# 7I92FPGA.net
KiCad netlist of a schematic drawn in Altium Designer
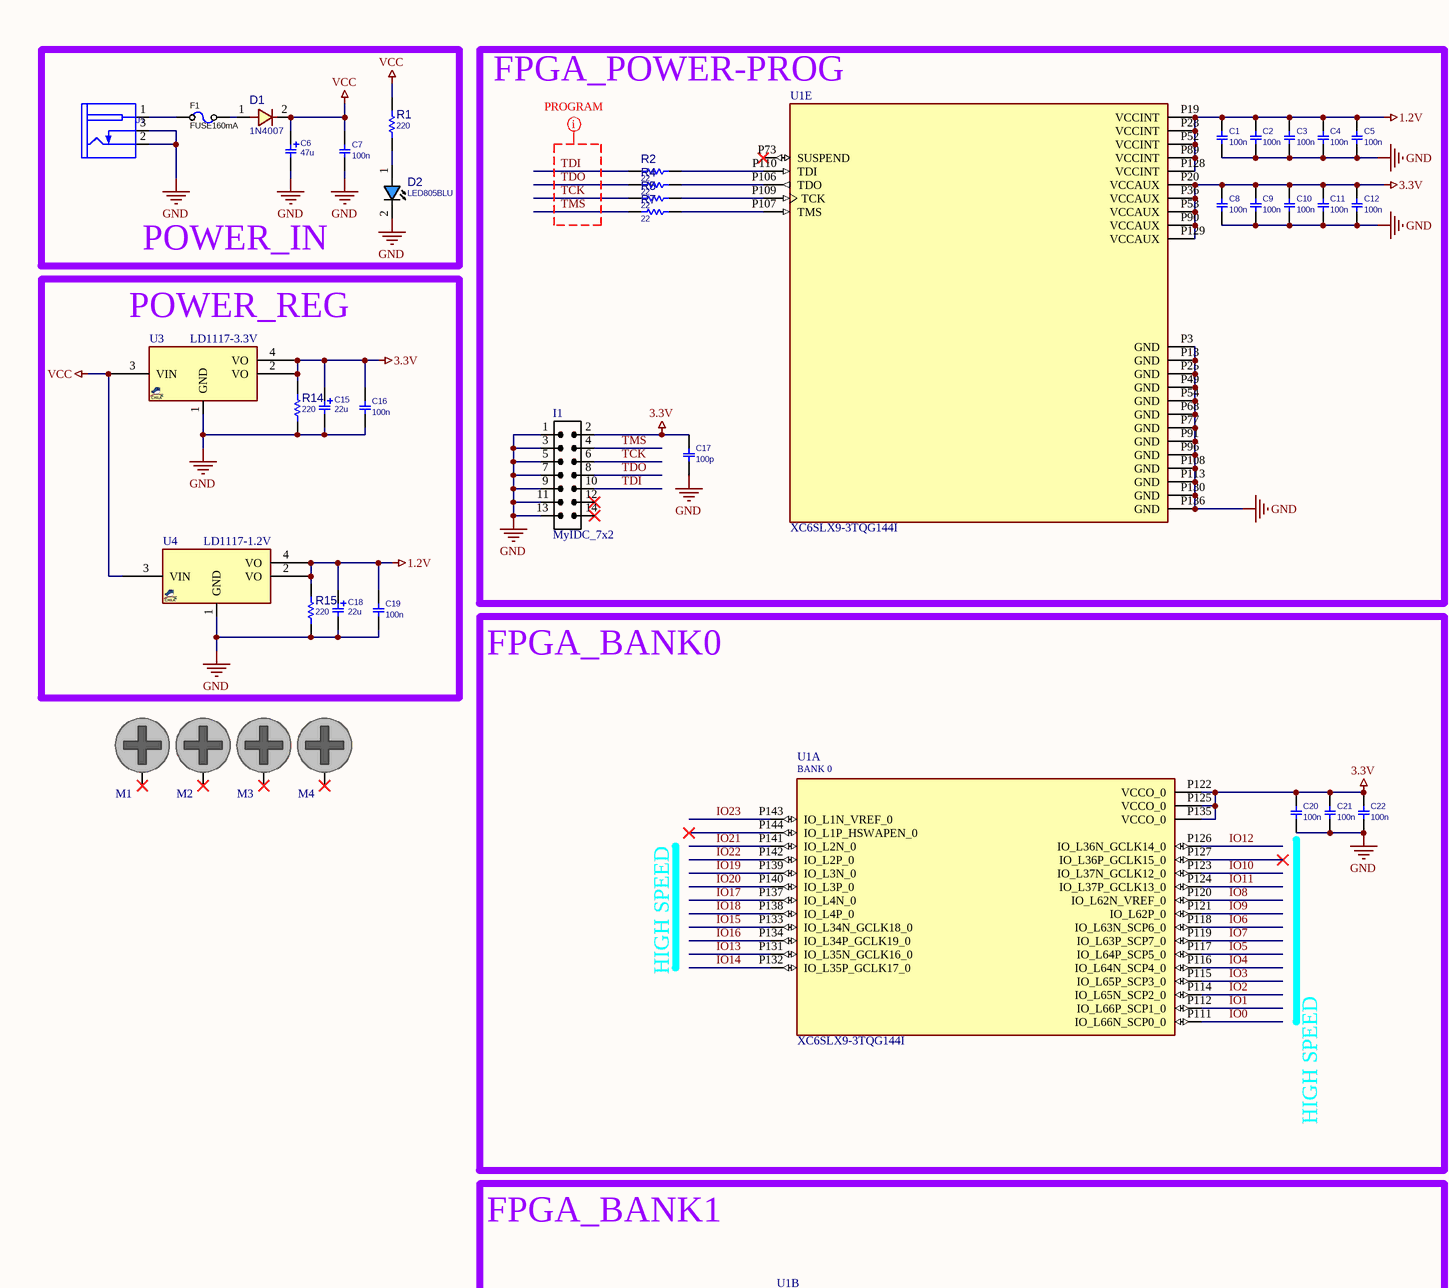
[diagram p0: 7I92FPGA.SchDoc, top left]
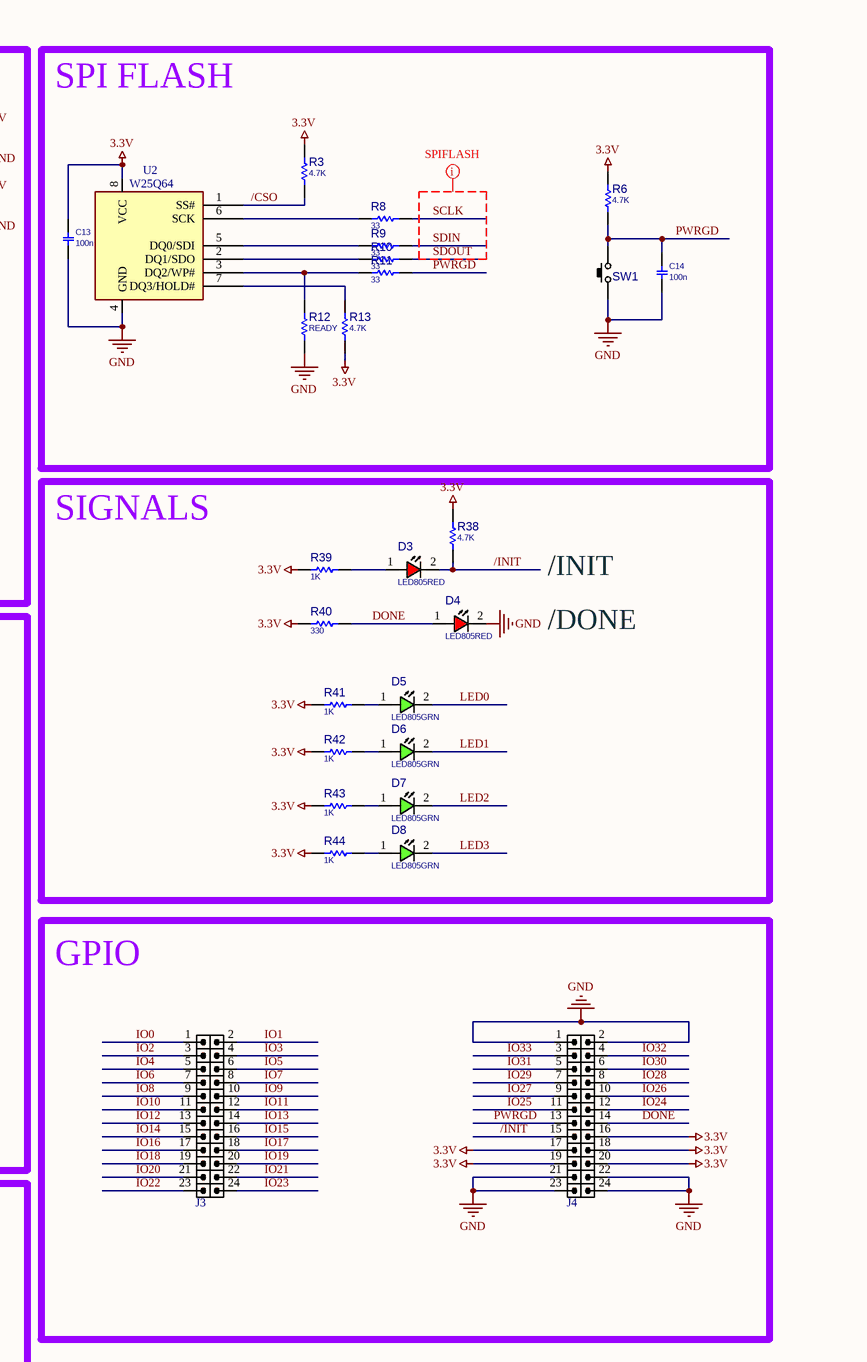
[diagram p1: 7I92FPGA.SchDoc, top middle]
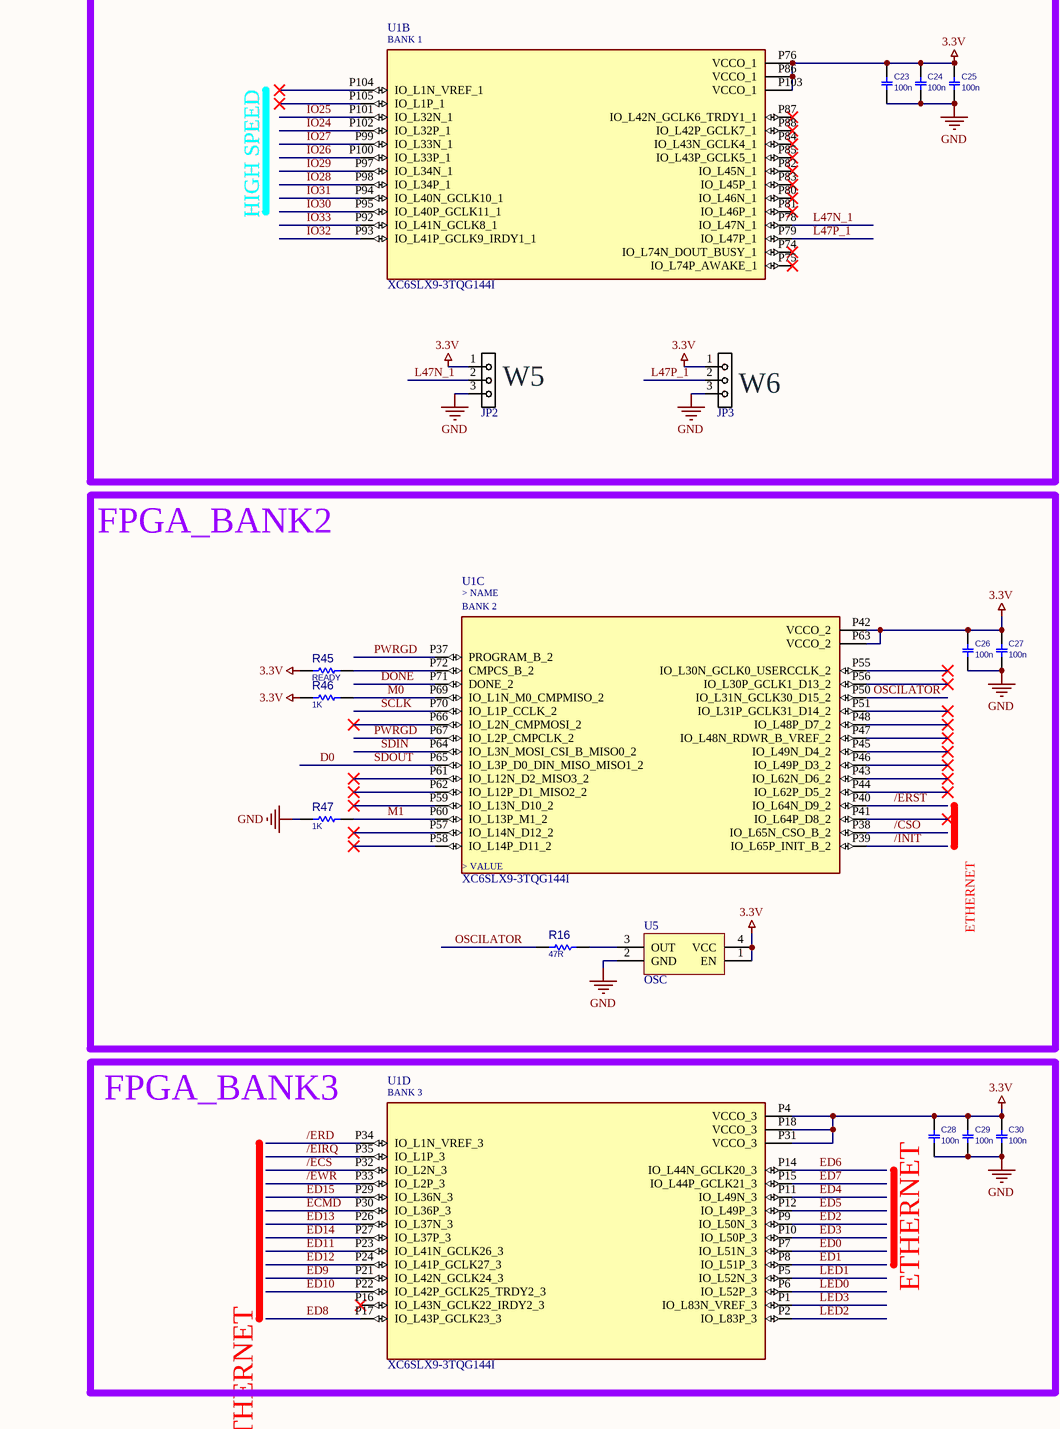
[diagram p2: 7I92FPGA.SchDoc, bottom left]
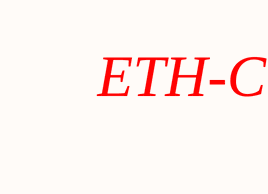
[diagram p3: 7I92FPGA.SchDoc, bottom right]

(export (version "E")
  (design (tool "Eeschema 10.0.6"))
  (components
    (comp (ref "C1")
      (value "100n")
      (footprint "C0603")
      (description "CAP, MLCC, 1nF, 50V, C0G, 10%, 0402")
      (fields (field (name "MANF") "Murata"))
      (libsource (lib "Full_libraries") (part "CAP_SMD_MLCC"))
    )
    (comp (ref "C2")
      (value "100n")
      (footprint "C0603")
      (description "CAP, MLCC, 1nF, 50V, C0G, 10%, 0402")
      (fields (field (name "MANF") "Murata"))
      (libsource (lib "Full_libraries") (part "CAP_SMD_MLCC"))
    )
    (comp (ref "C3")
      (value "100n")
      (footprint "C0603")
      (description "CAP, MLCC, 1nF, 50V, C0G, 10%, 0402")
      (fields (field (name "MANF") "Murata"))
      (libsource (lib "Full_libraries") (part "CAP_SMD_MLCC"))
    )
    (comp (ref "C4")
      (value "100n")
      (footprint "C0603")
      (description "CAP, MLCC, 1nF, 50V, C0G, 10%, 0402")
      (fields (field (name "MANF") "Murata"))
      (libsource (lib "Full_libraries") (part "CAP_SMD_MLCC"))
    )
    (comp (ref "C5")
      (value "100n")
      (footprint "C0603")
      (description "CAP, MLCC, 1nF, 50V, C0G, 10%, 0402")
      (fields (field (name "MANF") "Murata"))
      (libsource (lib "Full_libraries") (part "CAP_SMD_MLCC"))
    )
    (comp (ref "C6")
      (value "47u")
      (footprint "C_TN_3216")
      (description "CAP, SMD, TAN,")
      (libsource (lib "Full_libraries") (part "CAP_SMD_TAN"))
    )
    (comp (ref "C7")
      (value "100n")
      (footprint "C0805")
      (description "CAP, MLCC, 1nF, 50V, C0G, 10%, 0402")
      (fields (field (name "MANF") "Murata"))
      (libsource (lib "Full_libraries") (part "CAP_SMD_MLCC"))
    )
    (comp (ref "C8")
      (value "100n")
      (footprint "C0603")
      (description "CAP, MLCC, 1nF, 50V, C0G, 10%, 0402")
      (fields (field (name "MANF") "Murata"))
      (libsource (lib "Full_libraries") (part "CAP_SMD_MLCC"))
    )
    (comp (ref "C9")
      (value "100n")
      (footprint "C0603")
      (description "CAP, MLCC, 1nF, 50V, C0G, 10%, 0402")
      (fields (field (name "MANF") "Murata"))
      (libsource (lib "Full_libraries") (part "CAP_SMD_MLCC"))
    )
    (comp (ref "C10")
      (value "100n")
      (footprint "C0603")
      (description "CAP, MLCC, 1nF, 50V, C0G, 10%, 0402")
      (fields (field (name "MANF") "Murata"))
      (libsource (lib "Full_libraries") (part "CAP_SMD_MLCC"))
    )
    (comp (ref "C11")
      (value "100n")
      (footprint "C0603")
      (description "CAP, MLCC, 1nF, 50V, C0G, 10%, 0402")
      (fields (field (name "MANF") "Murata"))
      (libsource (lib "Full_libraries") (part "CAP_SMD_MLCC"))
    )
    (comp (ref "C12")
      (value "100n")
      (footprint "C0603")
      (description "CAP, MLCC, 1nF, 50V, C0G, 10%, 0402")
      (fields (field (name "MANF") "Murata"))
      (libsource (lib "Full_libraries") (part "CAP_SMD_MLCC"))
    )
    (comp (ref "C13")
      (value "100n")
      (footprint "C0603")
      (description "CAP, MLCC, 1nF, 50V, C0G, 10%, 0402")
      (fields (field (name "MANF") "Murata"))
      (libsource (lib "Full_libraries") (part "CAP_SMD_MLCC"))
    )
    (comp (ref "C14")
      (value "100n")
      (footprint "C0603")
      (description "CAP, MLCC, 1nF, 50V, C0G, 10%, 0402")
      (fields (field (name "MANF") "Murata"))
      (libsource (lib "Full_libraries") (part "CAP_SMD_MLCC"))
    )
    (comp (ref "C15")
      (value "22u")
      (footprint "C_TN_3216")
      (description "CAP, SMD, TAN,")
      (libsource (lib "Full_libraries") (part "CAP_SMD_TAN"))
    )
    (comp (ref "C16")
      (value "100n")
      (footprint "C0805")
      (description "CAP, MLCC, 1nF, 50V, C0G, 10%, 0402")
      (fields (field (name "MANF") "Murata"))
      (libsource (lib "Full_libraries") (part "CAP_SMD_MLCC"))
    )
    (comp (ref "C17")
      (value "100p")
      (footprint "C0603")
      (description "CAP, MLCC, 1nF, 50V, C0G, 10%, 0402")
      (fields (field (name "MANF") "Murata"))
      (libsource (lib "Full_libraries") (part "CAP_SMD_MLCC"))
    )
    (comp (ref "C18")
      (value "22u")
      (footprint "C_TN_3216")
      (description "CAP, SMD, TAN,")
      (libsource (lib "Full_libraries") (part "CAP_SMD_TAN"))
    )
    (comp (ref "C19")
      (value "100n")
      (footprint "C0805")
      (description "CAP, MLCC, 1nF, 50V, C0G, 10%, 0402")
      (fields (field (name "MANF") "Murata"))
      (libsource (lib "Full_libraries") (part "CAP_SMD_MLCC"))
    )
    (comp (ref "C20")
      (value "100n")
      (footprint "C0603")
      (description "CAP, MLCC, 1nF, 50V, C0G, 10%, 0402")
      (fields (field (name "MANF") "Murata"))
      (libsource (lib "Full_libraries") (part "CAP_SMD_MLCC"))
    )
    (comp (ref "C21")
      (value "100n")
      (footprint "C0603")
      (description "CAP, MLCC, 1nF, 50V, C0G, 10%, 0402")
      (fields (field (name "MANF") "Murata"))
      (libsource (lib "Full_libraries") (part "CAP_SMD_MLCC"))
    )
    (comp (ref "C22")
      (value "100n")
      (footprint "C0603")
      (description "CAP, MLCC, 1nF, 50V, C0G, 10%, 0402")
      (fields (field (name "MANF") "Murata"))
      (libsource (lib "Full_libraries") (part "CAP_SMD_MLCC"))
    )
    (comp (ref "C23")
      (value "100n")
      (footprint "C0603")
      (description "CAP, MLCC, 1nF, 50V, C0G, 10%, 0402")
      (fields (field (name "MANF") "Murata"))
      (libsource (lib "Full_libraries") (part "CAP_SMD_MLCC"))
    )
    (comp (ref "C24")
      (value "100n")
      (footprint "C0603")
      (description "CAP, MLCC, 1nF, 50V, C0G, 10%, 0402")
      (fields (field (name "MANF") "Murata"))
      (libsource (lib "Full_libraries") (part "CAP_SMD_MLCC"))
    )
    (comp (ref "C25")
      (value "100n")
      (footprint "C0603")
      (description "CAP, MLCC, 1nF, 50V, C0G, 10%, 0402")
      (fields (field (name "MANF") "Murata"))
      (libsource (lib "Full_libraries") (part "CAP_SMD_MLCC"))
    )
    (comp (ref "C26")
      (value "100n")
      (footprint "C0603")
      (description "CAP, MLCC, 1nF, 50V, C0G, 10%, 0402")
      (fields (field (name "MANF") "Murata"))
      (libsource (lib "Full_libraries") (part "CAP_SMD_MLCC"))
    )
    (comp (ref "C27")
      (value "100n")
      (footprint "C0603")
      (description "CAP, MLCC, 1nF, 50V, C0G, 10%, 0402")
      (fields (field (name "MANF") "Murata"))
      (libsource (lib "Full_libraries") (part "CAP_SMD_MLCC"))
    )
    (comp (ref "C28")
      (value "100n")
      (footprint "C0603")
      (description "CAP, MLCC, 1nF, 50V, C0G, 10%, 0402")
      (fields (field (name "MANF") "Murata"))
      (libsource (lib "Full_libraries") (part "CAP_SMD_MLCC"))
    )
    (comp (ref "C29")
      (value "100n")
      (footprint "C0603")
      (description "CAP, MLCC, 1nF, 50V, C0G, 10%, 0402")
      (fields (field (name "MANF") "Murata"))
      (libsource (lib "Full_libraries") (part "CAP_SMD_MLCC"))
    )
    (comp (ref "C30")
      (value "100n")
      (footprint "C0603")
      (description "CAP, MLCC, 1nF, 50V, C0G, 10%, 0402")
      (fields (field (name "MANF") "Murata"))
      (libsource (lib "Full_libraries") (part "CAP_SMD_MLCC"))
    )
    (comp (ref "D1")
      (value "1N4007")
      (footprint "D_SMA")
      (description "DIODE, GENERAL PURPOSE, 1000V/1A")
      (fields (field (name "MANF") "Kingtronics") (field (name "MANF_P#") "M7"))
      (libsource (lib "Full_libraries") (part "DIODE_SMD_1N4007"))
    )
    (comp (ref "D2")
      (value "LED805BLU")
      (footprint "LED0805BLU")
      (description "LED, SMD, 0805, BLUE")
      (fields (field (name "MANF") "MANF") (field (name "MANF_P#") "MANF_PART#"))
      (libsource (lib "Full_libraries") (part "LED_SMD_0805_BLU"))
    )
    (comp (ref "D3")
      (value "LED805RED")
      (footprint "LED0805RED")
      (description "LED, SMD, 0805, RED")
      (fields (field (name "MANF") "MANF") (field (name "MANF_P#") "MANF_PART#"))
      (libsource (lib "Full_libraries") (part "LED_SMD_0805_RED"))
    )
    (comp (ref "D4")
      (value "LED805RED")
      (footprint "LED0805RED")
      (description "LED, SMD, 0805, RED")
      (fields (field (name "MANF") "MANF") (field (name "MANF_P#") "MANF_PART#"))
      (libsource (lib "Full_libraries") (part "LED_SMD_0805_RED"))
    )
    (comp (ref "D5")
      (value "LED805GRN")
      (footprint "LED0805GRN")
      (description "LED, SMD, 0805, GREEN")
      (libsource (lib "Full_libraries") (part "LED_SMD_0805_GRN"))
    )
    (comp (ref "D6")
      (value "LED805GRN")
      (footprint "LED0805GRN")
      (description "LED, SMD, 0805, GREEN")
      (libsource (lib "Full_libraries") (part "LED_SMD_0805_GRN"))
    )
    (comp (ref "D7")
      (value "LED805GRN")
      (footprint "LED0805GRN")
      (description "LED, SMD, 0805, GREEN")
      (libsource (lib "Full_libraries") (part "LED_SMD_0805_GRN"))
    )
    (comp (ref "D8")
      (value "LED805GRN")
      (footprint "LED0805GRN")
      (description "LED, SMD, 0805, GREEN")
      (libsource (lib "Full_libraries") (part "LED_SMD_0805_GRN"))
    )
    (comp (ref "F1")
      (value "FUSE160mA")
      (footprint "F1206")
      (description "Fuse, 160mA, 63VDC, 1206, SMD, Fast Acting")
      (fields (field (name "MANF") "Holly Fuse") (field (name "MANF_P#") "12T-0160L"))
      (libsource (lib "Full_libraries") (part "FUSE_160mA_1206"))
    )
    (comp (ref "I1")
      (value "MyIDC_7x2")
      (footprint "myIDC_7x2")
      (libsource (lib "Full_libraries") (part "MyIDC_7x2"))
    )
    (comp (ref "J1")
      (value "DC_POWER_JACK")
      (footprint "JAC_PWR2")
      (description "CONN, PWR JACK DC, PLUG DIAM 2.0MM RA THD")
      (fields
        (field (name "MANF") "CUI STACK")
        (field (name "MANF_P#") "PJ-202A, PJ-002AH, PJ-102AH, KLDX-0202")
      )
      (libsource (lib "Full_libraries") (part "CONN_PWR_JACKR2"))
    )
    (comp (ref "J3")
      (value "HDRM_2X12")
      (footprint "HDR_M_2X12")
      (description "CONN, HEADER, Male, pitch: 2.54mm, 24POS")
      (libsource (lib "Full_libraries") (part "HDR_M_2X12"))
    )
    (comp (ref "J4")
      (value "HDRM_2X12")
      (footprint "HDR_M_2X12")
      (description "CONN, HEADER, Male, pitch: 2.54mm, 24POS")
      (libsource (lib "Full_libraries") (part "HDR_M_2X12"))
    )
    (comp (ref "JP2")
      (value "JMPHDR3PIN")
      (footprint "JP_3")
      (description "JUMPER, HEADER 3PIN")
      (fields (field (name "MANF") "MANF") (field (name "MANF_P#") "MANF_P#"))
      (libsource (lib "Full_libraries (1)") (part "JUMPER_HDR_3P"))
    )
    (comp (ref "JP3")
      (value "JMPHDR3PIN")
      (footprint "JP_3")
      (description "JUMPER, HEADER 3PIN")
      (fields (field (name "MANF") "MANF") (field (name "MANF_P#") "MANF_P#"))
      (libsource (lib "Full_libraries (1)") (part "JUMPER_HDR_3P"))
    )
    (comp (ref "M1")
      (value "DNP/MH")
      (footprint "SCMH_M4C")
      (description "SCREW mouting, M4, 4mm diameter and 8.0mm CheeseHead")
      (libsource (lib "Full_libraries") (part "SCMH_M4C"))
    )
    (comp (ref "M2")
      (value "DNP/MH")
      (footprint "SCMH_M4C")
      (description "SCREW mouting, M4, 4mm diameter and 8.0mm CheeseHead")
      (libsource (lib "Full_libraries") (part "SCMH_M4C"))
    )
    (comp (ref "M3")
      (value "DNP/MH")
      (footprint "SCMH_M4C")
      (description "SCREW mouting, M4, 4mm diameter and 8.0mm CheeseHead")
      (libsource (lib "Full_libraries") (part "SCMH_M4C"))
    )
    (comp (ref "M4")
      (value "DNP/MH")
      (footprint "SCMH_M4C")
      (description "SCREW mouting, M4, 4mm diameter and 8.0mm CheeseHead")
      (libsource (lib "Full_libraries") (part "SCMH_M4C"))
    )
    (comp (ref "R1")
      (value "220")
      (footprint "R0805")
      (description "RESISTOR, SMD")
      (fields (field (name "MANF_P#") "RK73H1ETTP4701F") (field (name "MANF") "KOA SPEER"))
      (libsource (lib "Full_libraries") (part "RES_SMD"))
    )
    (comp (ref "R2")
      (value "22")
      (footprint "R0603")
      (description "RESISTOR, SMD")
      (fields (field (name "MANF_P#") "RK73H1ETTP4701F") (field (name "MANF") "KOA SPEER"))
      (libsource (lib "Full_libraries") (part "RES_SMD"))
    )
    (comp (ref "R3")
      (value "4.7K")
      (footprint "R0603")
      (description "RESISTOR, SMD")
      (fields (field (name "MANF_P#") "RK73H1ETTP4701F") (field (name "MANF") "KOA SPEER"))
      (libsource (lib "Full_libraries") (part "RES_SMD"))
    )
    (comp (ref "R4")
      (value "22")
      (footprint "R0603")
      (description "RESISTOR, SMD")
      (fields (field (name "MANF_P#") "RK73H1ETTP4701F") (field (name "MANF") "KOA SPEER"))
      (libsource (lib "Full_libraries") (part "RES_SMD"))
    )
    (comp (ref "R5")
      (value "22")
      (footprint "R0603")
      (description "RESISTOR, SMD")
      (fields (field (name "MANF_P#") "RK73H1ETTP4701F") (field (name "MANF") "KOA SPEER"))
      (libsource (lib "Full_libraries") (part "RES_SMD"))
    )
    (comp (ref "R6")
      (value "4.7K")
      (footprint "R0603")
      (description "RESISTOR, SMD")
      (fields (field (name "MANF_P#") "RK73H1ETTP4701F") (field (name "MANF") "KOA SPEER"))
      (libsource (lib "Full_libraries") (part "RES_SMD"))
    )
    (comp (ref "R7")
      (value "22")
      (footprint "R0603")
      (description "RESISTOR, SMD")
      (fields (field (name "MANF_P#") "RK73H1ETTP4701F") (field (name "MANF") "KOA SPEER"))
      (libsource (lib "Full_libraries") (part "RES_SMD"))
    )
    (comp (ref "R8")
      (value "33")
      (footprint "R0603")
      (description "RESISTOR, SMD")
      (fields (field (name "MANF_P#") "RK73H1ETTP4701F") (field (name "MANF") "KOA SPEER"))
      (libsource (lib "Full_libraries") (part "RES_SMD"))
    )
    (comp (ref "R9")
      (value "33")
      (footprint "R0603")
      (description "RESISTOR, SMD")
      (fields (field (name "MANF_P#") "RK73H1ETTP4701F") (field (name "MANF") "KOA SPEER"))
      (libsource (lib "Full_libraries") (part "RES_SMD"))
    )
    (comp (ref "R10")
      (value "33")
      (footprint "R0603")
      (description "RESISTOR, SMD")
      (fields (field (name "MANF_P#") "RK73H1ETTP4701F") (field (name "MANF") "KOA SPEER"))
      (libsource (lib "Full_libraries") (part "RES_SMD"))
    )
    (comp (ref "R11")
      (value "33")
      (footprint "R0603")
      (description "RESISTOR, SMD")
      (fields (field (name "MANF_P#") "RK73H1ETTP4701F") (field (name "MANF") "KOA SPEER"))
      (libsource (lib "Full_libraries") (part "RES_SMD"))
    )
    (comp (ref "R12")
      (value "READY")
      (footprint "R0603")
      (description "RESISTOR, SMD")
      (fields (field (name "MANF_P#") "RK73H1ETTP4701F") (field (name "MANF") "KOA SPEER"))
      (libsource (lib "Full_libraries") (part "RES_SMD"))
    )
    (comp (ref "R13")
      (value "4.7K")
      (footprint "R0603")
      (description "RESISTOR, SMD")
      (fields (field (name "MANF_P#") "RK73H1ETTP4701F") (field (name "MANF") "KOA SPEER"))
      (libsource (lib "Full_libraries") (part "RES_SMD"))
    )
    (comp (ref "R14")
      (value "220")
      (footprint "R0805")
      (description "RESISTOR, SMD")
      (fields (field (name "MANF_P#") "RK73H1ETTP4701F") (field (name "MANF") "KOA SPEER"))
      (libsource (lib "Full_libraries") (part "RES_SMD"))
    )
    (comp (ref "R15")
      (value "220")
      (footprint "R0805")
      (description "RESISTOR, SMD")
      (fields (field (name "MANF_P#") "RK73H1ETTP4701F") (field (name "MANF") "KOA SPEER"))
      (libsource (lib "Full_libraries") (part "RES_SMD"))
    )
    (comp (ref "R16")
      (value "47R")
      (footprint "R0603")
      (description "RESISTOR, SMD")
      (fields (field (name "MANF_P#") "RK73H1ETTP4701F") (field (name "MANF") "KOA SPEER"))
      (libsource (lib "Full_libraries") (part "RES_SMD"))
    )
    (comp (ref "R38")
      (value "4.7K")
      (footprint "R0603")
      (description "RESISTOR, SMD")
      (fields (field (name "MANF_P#") "RK73H1ETTP4701F") (field (name "MANF") "KOA SPEER"))
      (libsource (lib "Full_libraries") (part "RES_SMD"))
    )
    (comp (ref "R39")
      (value "1K")
      (footprint "R0603")
      (description "RESISTOR, SMD")
      (fields (field (name "MANF_P#") "RK73H1ETTP4701F") (field (name "MANF") "KOA SPEER"))
      (libsource (lib "Full_libraries") (part "RES_SMD"))
    )
    (comp (ref "R40")
      (value "330")
      (footprint "R0603")
      (description "RESISTOR, SMD")
      (fields (field (name "MANF_P#") "RK73H1ETTP4701F") (field (name "MANF") "KOA SPEER"))
      (libsource (lib "Full_libraries") (part "RES_SMD"))
    )
    (comp (ref "R41")
      (value "1K")
      (footprint "R0603")
      (description "RESISTOR, SMD")
      (fields (field (name "MANF_P#") "RK73H1ETTP4701F") (field (name "MANF") "KOA SPEER"))
      (libsource (lib "Full_libraries") (part "RES_SMD"))
    )
    (comp (ref "R42")
      (value "1K")
      (footprint "R0603")
      (description "RESISTOR, SMD")
      (fields (field (name "MANF_P#") "RK73H1ETTP4701F") (field (name "MANF") "KOA SPEER"))
      (libsource (lib "Full_libraries") (part "RES_SMD"))
    )
    (comp (ref "R43")
      (value "1K")
      (footprint "R0603")
      (description "RESISTOR, SMD")
      (fields (field (name "MANF_P#") "RK73H1ETTP4701F") (field (name "MANF") "KOA SPEER"))
      (libsource (lib "Full_libraries") (part "RES_SMD"))
    )
    (comp (ref "R44")
      (value "1K")
      (footprint "R0603")
      (description "RESISTOR, SMD")
      (fields (field (name "MANF_P#") "RK73H1ETTP4701F") (field (name "MANF") "KOA SPEER"))
      (libsource (lib "Full_libraries") (part "RES_SMD"))
    )
    (comp (ref "R45")
      (value "READY")
      (footprint "R0603")
      (description "RESISTOR, SMD")
      (fields (field (name "MANF_P#") "RK73H1ETTP4701F") (field (name "MANF") "KOA SPEER"))
      (libsource (lib "Full_libraries") (part "RES_SMD"))
    )
    (comp (ref "R46")
      (value "1K")
      (footprint "R0603")
      (description "RESISTOR, SMD")
      (fields (field (name "MANF_P#") "RK73H1ETTP4701F") (field (name "MANF") "KOA SPEER"))
      (libsource (lib "Full_libraries") (part "RES_SMD"))
    )
    (comp (ref "R47")
      (value "1K")
      (footprint "R0603")
      (description "RESISTOR, SMD")
      (fields (field (name "MANF_P#") "RK73H1ETTP4701F") (field (name "MANF") "KOA SPEER"))
      (libsource (lib "Full_libraries") (part "RES_SMD"))
    )
    (comp (ref "SW1")
      (value "PUSHBUTTON")
      (footprint "SWPBS_SPST_6X3X5")
      (description "SWITCH, PUSH BUTTON, TACTILE, SMD, SPST, 6X3.5X4.3mm")
      (fields (field (name "MANF") "Panasonic") (field (name "MANF_P#") "EVQ-PNF04M"))
      (libsource (lib "Full_libraries") (part "SWPBS_SPST_6X3X4"))
    )
    (comp (ref "U1")
      (value "XC6SLX9-3TQG144I")
      (footprint "QFP50P2200X2200X160-144N")
      (description "FPGA Spartan-6 LX Family 9152 Cells 45nm (CMOS) Technology 1.2V 144-Pin TQFP")
      (fields (field (name "MF") "{'manufacturer': u'Xilinx Inc.'}"))
      (libsource (lib "SnapEDA_Library") (part "XC6SLX9-3TQG144I"))
    )
    (comp (ref "U2")
      (value "W25Q64")
      (footprint "SO_8_W")
      (description "SPI FLASH Memory, 64Mb (8M x8), 104MHz")
      (fields (field (name "MANF") "WINBOND") (field (name "MANF_P#") "W25Q64FVSSIG"))
      (libsource (lib "Full_libraries") (part "W25Q64FV_SO8W"))
    )
    (comp (ref "U3")
      (value "LD1117-3.3V")
      (footprint "SOT223_4")
      (description "REG, Linear, LDO1V, 0.8A, SOT-223")
      (fields
        (field (name "MANF_P#") "LD1117, LM1117, AMS1117, TLV1117, REG1117, NCP1117, LT1117, SPX1117")
        (field (name "MANF") "TI, ON, ST")
      )
      (libsource (lib "Full_libraries") (part "VREG_1117_SOT223"))
    )
    (comp (ref "U4")
      (value "LD1117-1.2V")
      (footprint "SOT223_4")
      (description "REG, Linear, LDO1V, 0.8A, SOT-223")
      (fields
        (field (name "MANF_P#") "LD1117, LM1117, AMS1117, TLV1117, REG1117, NCP1117, LT1117, SPX1117")
        (field (name "MANF") "TI, ON, ST")
      )
      (libsource (lib "Full_libraries") (part "VREG_1117_SOT223"))
    )
    (comp (ref "U5")
      (value "OSC")
      (footprint "XTL_4_7050GEN")
      (libsource (lib "Behyaar_RLCD_v1") (part "OSC (SMD)"))
    )
  )
  (nets
    (net (code "1") (name "/D0") (class "Default")
      (node (ref "R10") (pin "1") (pinfunction "1_1") (pintype "passive"))
      (node (ref "U1") (pin "P65") (pinfunction "IO_L3P_D0_DIN_MISO_MISO1_2_P65") (pintype "bidirectional"))
    )
    (net (code "2") (name "/DONE") (class "Default")
      (node (ref "D4") (pin "1") (pinfunction "ANODE_1") (pintype "passive"))
      (node (ref "J4") (pin "14") (pinfunction "14_14") (pintype "passive"))
      (node (ref "R40") (pin "1") (pinfunction "1_1") (pintype "passive"))
      (node (ref "U1") (pin "P71") (pinfunction "DONE_2_P71") (pintype "bidirectional"))
    )
    (net (code "3") (name "/ECMD") (class "Default")
      (node (ref "U1") (pin "P30") (pinfunction "IO_L36P_3_P30") (pintype "bidirectional"))
    )
    (net (code "4") (name "/ED0") (class "Default")
      (node (ref "U1") (pin "P7") (pinfunction "IO_L51N_3_P7") (pintype "bidirectional"))
    )
    (net (code "5") (name "/ED1") (class "Default")
      (node (ref "U1") (pin "P8") (pinfunction "IO_L51P_3_P8") (pintype "bidirectional"))
    )
    (net (code "6") (name "/ED2") (class "Default")
      (node (ref "U1") (pin "P9") (pinfunction "IO_L50N_3_P9") (pintype "bidirectional"))
    )
    (net (code "7") (name "/ED3") (class "Default")
      (node (ref "U1") (pin "P10") (pinfunction "IO_L50P_3_P10") (pintype "bidirectional"))
    )
    (net (code "8") (name "/ED4") (class "Default")
      (node (ref "U1") (pin "P11") (pinfunction "IO_L49N_3_P11") (pintype "bidirectional"))
    )
    (net (code "9") (name "/ED5") (class "Default")
      (node (ref "U1") (pin "P12") (pinfunction "IO_L49P_3_P12") (pintype "bidirectional"))
    )
    (net (code "10") (name "/ED6") (class "Default")
      (node (ref "U1") (pin "P14") (pinfunction "IO_L44N_GCLK20_3_P14") (pintype "bidirectional"))
    )
    (net (code "11") (name "/ED7") (class "Default")
      (node (ref "U1") (pin "P15") (pinfunction "IO_L44P_GCLK21_3_P15") (pintype "bidirectional"))
    )
    (net (code "12") (name "/ED8") (class "Default")
      (node (ref "U1") (pin "P17") (pinfunction "IO_L43P_GCLK23_3_P17") (pintype "bidirectional"))
    )
    (net (code "13") (name "/ED9") (class "Default")
      (node (ref "U1") (pin "P21") (pinfunction "IO_L42N_GCLK24_3_P21") (pintype "bidirectional"))
    )
    (net (code "14") (name "/ED10") (class "Default")
      (node (ref "U1") (pin "P22") (pinfunction "IO_L42P_GCLK25_TRDY2_3_P22") (pintype "bidirectional"))
    )
    (net (code "15") (name "/ED11") (class "Default")
      (node (ref "U1") (pin "P23") (pinfunction "IO_L41N_GCLK26_3_P23") (pintype "bidirectional"))
    )
    (net (code "16") (name "/ED12") (class "Default")
      (node (ref "U1") (pin "P24") (pinfunction "IO_L41P_GCLK27_3_P24") (pintype "bidirectional"))
    )
    (net (code "17") (name "/ED13") (class "Default")
      (node (ref "U1") (pin "P26") (pinfunction "IO_L37N_3_P26") (pintype "bidirectional"))
    )
    (net (code "18") (name "/ED14") (class "Default")
      (node (ref "U1") (pin "P27") (pinfunction "IO_L37P_3_P27") (pintype "bidirectional"))
    )
    (net (code "19") (name "/ED15") (class "Default")
      (node (ref "U1") (pin "P29") (pinfunction "IO_L36N_3_P29") (pintype "bidirectional"))
    )
    (net (code "20") (name "/IO0") (class "Default")
      (node (ref "J3") (pin "1") (pinfunction "1_1") (pintype "passive"))
      (node (ref "U1") (pin "P111") (pinfunction "IO_L66N_SCP0_0_P111") (pintype "bidirectional"))
    )
    (net (code "21") (name "/IO1") (class "Default")
      (node (ref "J3") (pin "2") (pinfunction "2_2") (pintype "passive"))
      (node (ref "U1") (pin "P112") (pinfunction "IO_L66P_SCP1_0_P112") (pintype "bidirectional"))
    )
    (net (code "22") (name "/IO2") (class "Default")
      (node (ref "J3") (pin "3") (pinfunction "3_3") (pintype "passive"))
      (node (ref "U1") (pin "P114") (pinfunction "IO_L65N_SCP2_0_P114") (pintype "bidirectional"))
    )
    (net (code "23") (name "/IO3") (class "Default")
      (node (ref "J3") (pin "4") (pinfunction "4_4") (pintype "passive"))
      (node (ref "U1") (pin "P115") (pinfunction "IO_L65P_SCP3_0_P115") (pintype "bidirectional"))
    )
    (net (code "24") (name "/IO4") (class "Default")
      (node (ref "J3") (pin "5") (pinfunction "5_5") (pintype "passive"))
      (node (ref "U1") (pin "P116") (pinfunction "IO_L64N_SCP4_0_P116") (pintype "bidirectional"))
    )
    (net (code "25") (name "/IO5") (class "Default")
      (node (ref "J3") (pin "6") (pinfunction "6_6") (pintype "passive"))
      (node (ref "U1") (pin "P117") (pinfunction "IO_L64P_SCP5_0_P117") (pintype "bidirectional"))
    )
    (net (code "26") (name "/IO6") (class "Default")
      (node (ref "J3") (pin "7") (pinfunction "7_7") (pintype "passive"))
      (node (ref "U1") (pin "P118") (pinfunction "IO_L63N_SCP6_0_P118") (pintype "bidirectional"))
    )
    (net (code "27") (name "/IO7") (class "Default")
      (node (ref "J3") (pin "8") (pinfunction "8_8") (pintype "passive"))
      (node (ref "U1") (pin "P119") (pinfunction "IO_L63P_SCP7_0_P119") (pintype "bidirectional"))
    )
    (net (code "28") (name "/IO8") (class "Default")
      (node (ref "J3") (pin "9") (pinfunction "9_9") (pintype "passive"))
      (node (ref "U1") (pin "P120") (pinfunction "IO_L62N_VREF_0_P120") (pintype "bidirectional"))
    )
    (net (code "29") (name "/IO9") (class "Default")
      (node (ref "J3") (pin "10") (pinfunction "10_10") (pintype "passive"))
      (node (ref "U1") (pin "P121") (pinfunction "IO_L62P_0_P121") (pintype "bidirectional"))
    )
    (net (code "30") (name "/IO10") (class "Default")
      (node (ref "J3") (pin "11") (pinfunction "11_11") (pintype "passive"))
      (node (ref "U1") (pin "P123") (pinfunction "IO_L37N_GCLK12_0_P123") (pintype "bidirectional"))
    )
    (net (code "31") (name "/IO11") (class "Default")
      (node (ref "J3") (pin "12") (pinfunction "12_12") (pintype "passive"))
      (node (ref "U1") (pin "P124") (pinfunction "IO_L37P_GCLK13_0_P124") (pintype "bidirectional"))
    )
    (net (code "32") (name "/IO12") (class "Default")
      (node (ref "J3") (pin "13") (pinfunction "13_13") (pintype "passive"))
      (node (ref "U1") (pin "P126") (pinfunction "IO_L36N_GCLK14_0_P126") (pintype "bidirectional"))
    )
    (net (code "33") (name "/IO13") (class "Default")
      (node (ref "J3") (pin "14") (pinfunction "14_14") (pintype "passive"))
      (node (ref "U1") (pin "P131") (pinfunction "IO_L35N_GCLK16_0_P131") (pintype "bidirectional"))
    )
    (net (code "34") (name "/IO14") (class "Default")
      (node (ref "J3") (pin "15") (pinfunction "15_15") (pintype "passive"))
      (node (ref "U1") (pin "P132") (pinfunction "IO_L35P_GCLK17_0_P132") (pintype "bidirectional"))
    )
    (net (code "35") (name "/IO15") (class "Default")
      (node (ref "J3") (pin "16") (pinfunction "16_16") (pintype "passive"))
      (node (ref "U1") (pin "P133") (pinfunction "IO_L34N_GCLK18_0_P133") (pintype "bidirectional"))
    )
    (net (code "36") (name "/IO16") (class "Default")
      (node (ref "J3") (pin "17") (pinfunction "17_17") (pintype "passive"))
      (node (ref "U1") (pin "P134") (pinfunction "IO_L34P_GCLK19_0_P134") (pintype "bidirectional"))
    )
    (net (code "37") (name "/IO17") (class "Default")
      (node (ref "J3") (pin "18") (pinfunction "18_18") (pintype "passive"))
      (node (ref "U1") (pin "P137") (pinfunction "IO_L4N_0_P137") (pintype "bidirectional"))
    )
    (net (code "38") (name "/IO18") (class "Default")
      (node (ref "J3") (pin "19") (pinfunction "19_19") (pintype "passive"))
      (node (ref "U1") (pin "P138") (pinfunction "IO_L4P_0_P138") (pintype "bidirectional"))
    )
    (net (code "39") (name "/IO19") (class "Default")
      (node (ref "J3") (pin "20") (pinfunction "20_20") (pintype "passive"))
      (node (ref "U1") (pin "P139") (pinfunction "IO_L3N_0_P139") (pintype "bidirectional"))
    )
    (net (code "40") (name "/IO20") (class "Default")
      (node (ref "J3") (pin "21") (pinfunction "21_21") (pintype "passive"))
      (node (ref "U1") (pin "P140") (pinfunction "IO_L3P_0_P140") (pintype "bidirectional"))
    )
    (net (code "41") (name "/IO21") (class "Default")
      (node (ref "J3") (pin "22") (pinfunction "22_22") (pintype "passive"))
      (node (ref "U1") (pin "P141") (pinfunction "IO_L2N_0_P141") (pintype "bidirectional"))
    )
    (net (code "42") (name "/IO22") (class "Default")
      (node (ref "J3") (pin "23") (pinfunction "23_23") (pintype "passive"))
      (node (ref "U1") (pin "P142") (pinfunction "IO_L2P_0_P142") (pintype "bidirectional"))
    )
    (net (code "43") (name "/IO23") (class "Default")
      (node (ref "J3") (pin "24") (pinfunction "24_24") (pintype "passive"))
      (node (ref "U1") (pin "P143") (pinfunction "IO_L1N_VREF_0_P143") (pintype "bidirectional"))
    )
    (net (code "44") (name "/IO24") (class "Default")
      (node (ref "J4") (pin "12") (pinfunction "12_12") (pintype "passive"))
      (node (ref "U1") (pin "P102") (pinfunction "IO_L32P_1_P102") (pintype "bidirectional"))
    )
    (net (code "45") (name "/IO25") (class "Default")
      (node (ref "J4") (pin "11") (pinfunction "11_11") (pintype "passive"))
      (node (ref "U1") (pin "P101") (pinfunction "IO_L32N_1_P101") (pintype "bidirectional"))
    )
    (net (code "46") (name "/IO26") (class "Default")
      (node (ref "J4") (pin "10") (pinfunction "10_10") (pintype "passive"))
      (node (ref "U1") (pin "P100") (pinfunction "IO_L33P_1_P100") (pintype "bidirectional"))
    )
    (net (code "47") (name "/IO27") (class "Default")
      (node (ref "J4") (pin "9") (pinfunction "9_9") (pintype "passive"))
      (node (ref "U1") (pin "P99") (pinfunction "IO_L33N_1_P99") (pintype "bidirectional"))
    )
    (net (code "48") (name "/IO28") (class "Default")
      (node (ref "J4") (pin "8") (pinfunction "8_8") (pintype "passive"))
      (node (ref "U1") (pin "P98") (pinfunction "IO_L34P_1_P98") (pintype "bidirectional"))
    )
    (net (code "49") (name "/IO29") (class "Default")
      (node (ref "J4") (pin "7") (pinfunction "7_7") (pintype "passive"))
      (node (ref "U1") (pin "P97") (pinfunction "IO_L34N_1_P97") (pintype "bidirectional"))
    )
    (net (code "50") (name "/IO30") (class "Default")
      (node (ref "J4") (pin "6") (pinfunction "6_6") (pintype "passive"))
      (node (ref "U1") (pin "P95") (pinfunction "IO_L40P_GCLK11_1_P95") (pintype "bidirectional"))
    )
    (net (code "51") (name "/IO31") (class "Default")
      (node (ref "J4") (pin "5") (pinfunction "5_5") (pintype "passive"))
      (node (ref "U1") (pin "P94") (pinfunction "IO_L40N_GCLK10_1_P94") (pintype "bidirectional"))
    )
    (net (code "52") (name "/IO32") (class "Default")
      (node (ref "J4") (pin "4") (pinfunction "4_4") (pintype "passive"))
      (node (ref "U1") (pin "P93") (pinfunction "IO_L41P_GCLK9_IRDY1_1_P93") (pintype "bidirectional"))
    )
    (net (code "53") (name "/IO33") (class "Default")
      (node (ref "J4") (pin "3") (pinfunction "3_3") (pintype "passive"))
      (node (ref "U1") (pin "P92") (pinfunction "IO_L41N_GCLK8_1_P92") (pintype "bidirectional"))
    )
    (net (code "54") (name "/L47N_1") (class "Default")
      (node (ref "JP2") (pin "2") (pinfunction "2_2") (pintype "passive"))
      (node (ref "U1") (pin "P78") (pinfunction "IO_L47N_1_P78") (pintype "bidirectional"))
    )
    (net (code "55") (name "/L47P_1") (class "Default")
      (node (ref "JP3") (pin "2") (pinfunction "2_2") (pintype "passive"))
      (node (ref "U1") (pin "P79") (pinfunction "IO_L47P_1_P79") (pintype "bidirectional"))
    )
    (net (code "56") (name "/LED0") (class "Default")
      (node (ref "D5") (pin "2") (pinfunction "CATHODE_2") (pintype "passive"))
      (node (ref "U1") (pin "P6") (pinfunction "IO_L52P_3_P6") (pintype "bidirectional"))
    )
    (net (code "57") (name "/LED1") (class "Default")
      (node (ref "D6") (pin "2") (pinfunction "CATHODE_2") (pintype "passive"))
      (node (ref "U1") (pin "P5") (pinfunction "IO_L52N_3_P5") (pintype "bidirectional"))
    )
    (net (code "58") (name "/LED2") (class "Default")
      (node (ref "D7") (pin "2") (pinfunction "CATHODE_2") (pintype "passive"))
      (node (ref "U1") (pin "P2") (pinfunction "IO_L83P_3_P2") (pintype "bidirectional"))
    )
    (net (code "59") (name "/LED3") (class "Default")
      (node (ref "D8") (pin "2") (pinfunction "CATHODE_2") (pintype "passive"))
      (node (ref "U1") (pin "P1") (pinfunction "IO_L83N_VREF_3_P1") (pintype "bidirectional"))
    )
    (net (code "60") (name "/M0") (class "Default")
      (node (ref "R46") (pin "1") (pinfunction "1_1") (pintype "passive"))
      (node (ref "U1") (pin "P69") (pinfunction "IO_L1N_M0_CMPMISO_2_P69") (pintype "bidirectional"))
    )
    (net (code "61") (name "/M1") (class "Default")
      (node (ref "R47") (pin "1") (pinfunction "1_1") (pintype "passive"))
      (node (ref "U1") (pin "P60") (pinfunction "IO_L13P_M1_2_P60") (pintype "bidirectional"))
    )
    (net (code "62") (name "/OSCILATOR") (class "Default")
      (node (ref "R16") (pin "1") (pinfunction "1_1") (pintype "passive"))
      (node (ref "U1") (pin "P50") (pinfunction "IO_L31N_GCLK30_D15_2_P50") (pintype "bidirectional"))
    )
    (net (code "63") (name "/PWRGD") (class "Default")
      (node (ref "C14") (pin "1") (pinfunction "1_1") (pintype "passive"))
      (node (ref "J4") (pin "13") (pinfunction "13_13") (pintype "passive"))
      (node (ref "R11") (pin "1") (pinfunction "1_1") (pintype "passive"))
      (node (ref "R6") (pin "1") (pinfunction "1_1") (pintype "passive"))
      (node (ref "SW1") (pin "2") (pinfunction "P3_2") (pintype "passive"))
      (node (ref "U1") (pin "P37") (pinfunction "PROGRAM_B_2_P37") (pintype "bidirectional"))
      (node (ref "U1") (pin "P67") (pinfunction "IO_L2P_CMPCLK_2_P67") (pintype "bidirectional"))
    )
    (net (code "64") (name "/SCLK") (class "Default")
      (node (ref "R8") (pin "1") (pinfunction "1_1") (pintype "passive"))
      (node (ref "U1") (pin "P70") (pinfunction "IO_L1P_CCLK_2_P70") (pintype "bidirectional"))
    )
    (net (code "65") (name "/SDIN") (class "Default")
      (node (ref "R9") (pin "1") (pinfunction "1_1") (pintype "passive"))
      (node (ref "U1") (pin "P64") (pinfunction "IO_L3N_MOSI_CSI_B_MISO0_2_P64") (pintype "bidirectional"))
    )
    (net (code "66") (name "/TCK") (class "Default")
      (node (ref "I1") (pin "6") (pinfunction "6_6") (pintype "passive"))
      (node (ref "R5") (pin "2") (pinfunction "2_2") (pintype "passive"))
    )
    (net (code "67") (name "/TDI") (class "Default")
      (node (ref "I1") (pin "10") (pinfunction "10_10") (pintype "passive"))
      (node (ref "R2") (pin "2") (pinfunction "2_2") (pintype "passive"))
    )
    (net (code "68") (name "/TDO") (class "Default")
      (node (ref "I1") (pin "8") (pinfunction "8_8") (pintype "passive"))
      (node (ref "R4") (pin "2") (pinfunction "2_2") (pintype "passive"))
    )
    (net (code "69") (name "/TMS") (class "Default")
      (node (ref "I1") (pin "4") (pinfunction "4_4") (pintype "passive"))
      (node (ref "R7") (pin "2") (pinfunction "2_2") (pintype "passive"))
    )
    (net (code "70") (name "/{slash}CSO") (class "Default")
      (node (ref "R3") (pin "1") (pinfunction "1_1") (pintype "passive"))
      (node (ref "U1") (pin "P38") (pinfunction "IO_L65N_CSO_B_2_P38") (pintype "bidirectional"))
      (node (ref "U2") (pin "1") (pinfunction "SS#_1") (pintype "passive"))
    )
    (net (code "71") (name "/{slash}ECS") (class "Default")
      (node (ref "U1") (pin "P32") (pinfunction "IO_L2N_3_P32") (pintype "bidirectional"))
    )
    (net (code "72") (name "/{slash}EIRQ") (class "Default")
      (node (ref "U1") (pin "P35") (pinfunction "IO_L1P_3_P35") (pintype "bidirectional"))
    )
    (net (code "73") (name "/{slash}ERD") (class "Default")
      (node (ref "U1") (pin "P34") (pinfunction "IO_L1N_VREF_3_P34") (pintype "bidirectional"))
    )
    (net (code "74") (name "/{slash}ERST") (class "Default")
      (node (ref "U1") (pin "P40") (pinfunction "IO_L64N_D9_2_P40") (pintype "bidirectional"))
    )
    (net (code "75") (name "/{slash}EWR") (class "Default")
      (node (ref "U1") (pin "P33") (pinfunction "IO_L2P_3_P33") (pintype "bidirectional"))
    )
    (net (code "76") (name "/{slash}INIT") (class "Default")
      (node (ref "D3") (pin "2") (pinfunction "CATHODE_2") (pintype "passive"))
      (node (ref "J4") (pin "15") (pinfunction "15_15") (pintype "passive"))
      (node (ref "R38") (pin "2") (pinfunction "2_2") (pintype "passive"))
      (node (ref "U1") (pin "P39") (pinfunction "IO_L65P_INIT_B_2_P39") (pintype "bidirectional"))
    )
    (net (code "77") (name "1.2V") (class "Default")
      (node (ref "C1") (pin "1") (pinfunction "1_1") (pintype "passive"))
      (node (ref "C18") (pin "1") (pinfunction "1_1") (pintype "passive"))
      (node (ref "C19") (pin "1") (pinfunction "1_1") (pintype "passive"))
      (node (ref "C2") (pin "1") (pinfunction "1_1") (pintype "passive"))
      (node (ref "C3") (pin "1") (pinfunction "1_1") (pintype "passive"))
      (node (ref "C4") (pin "1") (pinfunction "1_1") (pintype "passive"))
      (node (ref "C5") (pin "1") (pinfunction "1_1") (pintype "passive"))
      (node (ref "R15") (pin "1") (pinfunction "1_1") (pintype "passive"))
      (node (ref "U1") (pin "P128") (pinfunction "VCCINT_P128") (pintype "power_in"))
      (node (ref "U1") (pin "P19") (pinfunction "VCCINT_P19") (pintype "power_in"))
      (node (ref "U1") (pin "P28") (pinfunction "VCCINT_P28") (pintype "power_in"))
      (node (ref "U1") (pin "P52") (pinfunction "VCCINT_P52") (pintype "power_in"))
      (node (ref "U1") (pin "P89") (pinfunction "VCCINT_P89") (pintype "power_in"))
      (node (ref "U4") (pin "2") (pinfunction "VO_2") (pintype "passive"))
      (node (ref "U4") (pin "4") (pinfunction "VO_4") (pintype "passive"))
    )
    (net (code "78") (name "3.3V") (class "Default")
      (node (ref "C10") (pin "1") (pinfunction "1_1") (pintype "passive"))
      (node (ref "C11") (pin "1") (pinfunction "1_1") (pintype "passive"))
      (node (ref "C12") (pin "1") (pinfunction "1_1") (pintype "passive"))
      (node (ref "C13") (pin "1") (pinfunction "1_1") (pintype "passive"))
      (node (ref "C15") (pin "1") (pinfunction "1_1") (pintype "passive"))
      (node (ref "C16") (pin "1") (pinfunction "1_1") (pintype "passive"))
      (node (ref "C17") (pin "1") (pinfunction "1_1") (pintype "passive"))
      (node (ref "C20") (pin "1") (pinfunction "1_1") (pintype "passive"))
      (node (ref "C21") (pin "1") (pinfunction "1_1") (pintype "passive"))
      (node (ref "C22") (pin "1") (pinfunction "1_1") (pintype "passive"))
      (node (ref "C23") (pin "1") (pinfunction "1_1") (pintype "passive"))
      (node (ref "C24") (pin "1") (pinfunction "1_1") (pintype "passive"))
      (node (ref "C25") (pin "1") (pinfunction "1_1") (pintype "passive"))
      (node (ref "C26") (pin "1") (pinfunction "1_1") (pintype "passive"))
      (node (ref "C27") (pin "1") (pinfunction "1_1") (pintype "passive"))
      (node (ref "C28") (pin "1") (pinfunction "1_1") (pintype "passive"))
      (node (ref "C29") (pin "1") (pinfunction "1_1") (pintype "passive"))
      (node (ref "C30") (pin "1") (pinfunction "1_1") (pintype "passive"))
      (node (ref "C8") (pin "1") (pinfunction "1_1") (pintype "passive"))
      (node (ref "C9") (pin "1") (pinfunction "1_1") (pintype "passive"))
      (node (ref "I1") (pin "2") (pinfunction "2_2") (pintype "passive"))
      (node (ref "J4") (pin "16") (pinfunction "16_16") (pintype "passive"))
      (node (ref "J4") (pin "17") (pinfunction "17_17") (pintype "passive"))
      (node (ref "J4") (pin "18") (pinfunction "18_18") (pintype "passive"))
      (node (ref "J4") (pin "19") (pinfunction "19_19") (pintype "passive"))
      (node (ref "J4") (pin "20") (pinfunction "20_20") (pintype "passive"))
      (node (ref "JP2") (pin "1") (pinfunction "1_1") (pintype "passive"))
      (node (ref "JP3") (pin "1") (pinfunction "1_1") (pintype "passive"))
      (node (ref "R13") (pin "1") (pinfunction "1_1") (pintype "passive"))
      (node (ref "R14") (pin "1") (pinfunction "1_1") (pintype "passive"))
      (node (ref "R3") (pin "2") (pinfunction "2_2") (pintype "passive"))
      (node (ref "R38") (pin "1") (pinfunction "1_1") (pintype "passive"))
      (node (ref "R39") (pin "2") (pinfunction "2_2") (pintype "passive"))
      (node (ref "R40") (pin "2") (pinfunction "2_2") (pintype "passive"))
      (node (ref "R41") (pin "2") (pinfunction "2_2") (pintype "passive"))
      (node (ref "R42") (pin "2") (pinfunction "2_2") (pintype "passive"))
      (node (ref "R43") (pin "2") (pinfunction "2_2") (pintype "passive"))
      (node (ref "R44") (pin "2") (pinfunction "2_2") (pintype "passive"))
      (node (ref "R45") (pin "2") (pinfunction "2_2") (pintype "passive"))
      (node (ref "R46") (pin "2") (pinfunction "2_2") (pintype "passive"))
      (node (ref "R6") (pin "2") (pinfunction "2_2") (pintype "passive"))
      (node (ref "U1") (pin "P103") (pinfunction "VCCO_1_P103") (pintype "power_in"))
      (node (ref "U1") (pin "P122") (pinfunction "VCCO_0_P122") (pintype "power_in"))
      (node (ref "U1") (pin "P125") (pinfunction "VCCO_0_P125") (pintype "power_in"))
      (node (ref "U1") (pin "P129") (pinfunction "VCCAUX_P129") (pintype "power_in"))
      (node (ref "U1") (pin "P135") (pinfunction "VCCO_0_P135") (pintype "power_in"))
      (node (ref "U1") (pin "P18") (pinfunction "VCCO_3_P18") (pintype "power_in"))
      (node (ref "U1") (pin "P20") (pinfunction "VCCAUX_P20") (pintype "power_in"))
      (node (ref "U1") (pin "P31") (pinfunction "VCCO_3_P31") (pintype "power_in"))
      (node (ref "U1") (pin "P36") (pinfunction "VCCAUX_P36") (pintype "power_in"))
      (node (ref "U1") (pin "P4") (pinfunction "VCCO_3_P4") (pintype "power_in"))
      (node (ref "U1") (pin "P42") (pinfunction "VCCO_2_P42") (pintype "power_in"))
      (node (ref "U1") (pin "P53") (pinfunction "VCCAUX_P53") (pintype "power_in"))
      (node (ref "U1") (pin "P63") (pinfunction "VCCO_2_P63") (pintype "power_in"))
      (node (ref "U1") (pin "P76") (pinfunction "VCCO_1_P76") (pintype "power_in"))
      (node (ref "U1") (pin "P86") (pinfunction "VCCO_1_P86") (pintype "power_in"))
      (node (ref "U1") (pin "P90") (pinfunction "VCCAUX_P90") (pintype "power_in"))
      (node (ref "U2") (pin "8") (pinfunction "VCC_8") (pintype "passive"))
      (node (ref "U3") (pin "2") (pinfunction "VO_2") (pintype "passive"))
      (node (ref "U3") (pin "4") (pinfunction "VO_4") (pintype "passive"))
      (node (ref "U5") (pin "1") (pinfunction "EN_1") (pintype "passive"))
      (node (ref "U5") (pin "4") (pinfunction "VCC_4") (pintype "passive"))
    )
    (net (code "79") (name "GND") (class "Default")
      (node (ref "C1") (pin "2") (pinfunction "2_2") (pintype "passive"))
      (node (ref "C10") (pin "2") (pinfunction "2_2") (pintype "passive"))
      (node (ref "C11") (pin "2") (pinfunction "2_2") (pintype "passive"))
      (node (ref "C12") (pin "2") (pinfunction "2_2") (pintype "passive"))
      (node (ref "C13") (pin "2") (pinfunction "2_2") (pintype "passive"))
      (node (ref "C14") (pin "2") (pinfunction "2_2") (pintype "passive"))
      (node (ref "C15") (pin "2") (pinfunction "2_2") (pintype "passive"))
      (node (ref "C16") (pin "2") (pinfunction "2_2") (pintype "passive"))
      (node (ref "C17") (pin "2") (pinfunction "2_2") (pintype "passive"))
      (node (ref "C18") (pin "2") (pinfunction "2_2") (pintype "passive"))
      (node (ref "C19") (pin "2") (pinfunction "2_2") (pintype "passive"))
      (node (ref "C2") (pin "2") (pinfunction "2_2") (pintype "passive"))
      (node (ref "C20") (pin "2") (pinfunction "2_2") (pintype "passive"))
      (node (ref "C21") (pin "2") (pinfunction "2_2") (pintype "passive"))
      (node (ref "C22") (pin "2") (pinfunction "2_2") (pintype "passive"))
      (node (ref "C23") (pin "2") (pinfunction "2_2") (pintype "passive"))
      (node (ref "C24") (pin "2") (pinfunction "2_2") (pintype "passive"))
      (node (ref "C25") (pin "2") (pinfunction "2_2") (pintype "passive"))
      (node (ref "C26") (pin "2") (pinfunction "2_2") (pintype "passive"))
      (node (ref "C27") (pin "2") (pinfunction "2_2") (pintype "passive"))
      (node (ref "C28") (pin "2") (pinfunction "2_2") (pintype "passive"))
      (node (ref "C29") (pin "2") (pinfunction "2_2") (pintype "passive"))
      (node (ref "C3") (pin "2") (pinfunction "2_2") (pintype "passive"))
      (node (ref "C30") (pin "2") (pinfunction "2_2") (pintype "passive"))
      (node (ref "C4") (pin "2") (pinfunction "2_2") (pintype "passive"))
      (node (ref "C5") (pin "2") (pinfunction "2_2") (pintype "passive"))
      (node (ref "C6") (pin "2") (pinfunction "2_2") (pintype "passive"))
      (node (ref "C7") (pin "2") (pinfunction "2_2") (pintype "passive"))
      (node (ref "C8") (pin "2") (pinfunction "2_2") (pintype "passive"))
      (node (ref "C9") (pin "2") (pinfunction "2_2") (pintype "passive"))
      (node (ref "D2") (pin "2") (pinfunction "CATHODE_2") (pintype "passive"))
      (node (ref "D4") (pin "2") (pinfunction "CATHODE_2") (pintype "passive"))
      (node (ref "I1") (pin "1") (pinfunction "1_1") (pintype "passive"))
      (node (ref "I1") (pin "11") (pinfunction "11_11") (pintype "passive"))
      (node (ref "I1") (pin "13") (pinfunction "13_13") (pintype "passive"))
      (node (ref "I1") (pin "3") (pinfunction "3_3") (pintype "passive"))
      (node (ref "I1") (pin "5") (pinfunction "5_5") (pintype "passive"))
      (node (ref "I1") (pin "7") (pinfunction "7_7") (pintype "passive"))
      (node (ref "I1") (pin "9") (pinfunction "9_9") (pintype "passive"))
      (node (ref "J1") (pin "2") (pinfunction "SLEEVE_2") (pintype "power_in"))
      (node (ref "J1") (pin "3") (pinfunction "INSERTION_DET_3") (pintype "power_in"))
      (node (ref "J4") (pin "1") (pinfunction "1_1") (pintype "passive"))
      (node (ref "J4") (pin "2") (pinfunction "2_2") (pintype "passive"))
      (node (ref "J4") (pin "21") (pinfunction "21_21") (pintype "passive"))
      (node (ref "J4") (pin "22") (pinfunction "22_22") (pintype "passive"))
      (node (ref "J4") (pin "23") (pinfunction "23_23") (pintype "passive"))
      (node (ref "J4") (pin "24") (pinfunction "24_24") (pintype "passive"))
      (node (ref "JP2") (pin "3") (pinfunction "3_3") (pintype "passive"))
      (node (ref "JP3") (pin "3") (pinfunction "3_3") (pintype "passive"))
      (node (ref "R12") (pin "1") (pinfunction "1_1") (pintype "passive"))
      (node (ref "R14") (pin "2") (pinfunction "2_2") (pintype "passive"))
      (node (ref "R15") (pin "2") (pinfunction "2_2") (pintype "passive"))
      (node (ref "R47") (pin "2") (pinfunction "2_2") (pintype "passive"))
      (node (ref "SW1") (pin "1") (pinfunction "P1_1") (pintype "passive"))
      (node (ref "U1") (pin "P108") (pinfunction "GND_P108") (pintype "power_in"))
      (node (ref "U1") (pin "P113") (pinfunction "GND_P113") (pintype "power_in"))
      (node (ref "U1") (pin "P13") (pinfunction "GND_P13") (pintype "power_in"))
      (node (ref "U1") (pin "P130") (pinfunction "GND_P130") (pintype "power_in"))
      (node (ref "U1") (pin "P136") (pinfunction "GND_P136") (pintype "power_in"))
      (node (ref "U1") (pin "P25") (pinfunction "GND_P25") (pintype "power_in"))
      (node (ref "U1") (pin "P3") (pinfunction "GND_P3") (pintype "power_in"))
      (node (ref "U1") (pin "P49") (pinfunction "GND_P49") (pintype "power_in"))
      (node (ref "U1") (pin "P54") (pinfunction "GND_P54") (pintype "power_in"))
      (node (ref "U1") (pin "P68") (pinfunction "GND_P68") (pintype "power_in"))
      (node (ref "U1") (pin "P77") (pinfunction "GND_P77") (pintype "power_in"))
      (node (ref "U1") (pin "P91") (pinfunction "GND_P91") (pintype "power_in"))
      (node (ref "U1") (pin "P96") (pinfunction "GND_P96") (pintype "power_in"))
      (node (ref "U2") (pin "4") (pinfunction "GND_4") (pintype "passive"))
      (node (ref "U3") (pin "1") (pinfunction "GND_1") (pintype "passive"))
      (node (ref "U4") (pin "1") (pinfunction "GND_1") (pintype "passive"))
      (node (ref "U5") (pin "2") (pinfunction "GND_2") (pintype "passive"))
    )
    (net (code "80") (name "Net-(D1-Pad1)") (class "Default")
      (node (ref "D1") (pin "1") (pinfunction "1_1") (pintype "passive"))
      (node (ref "F1") (pin "2") (pinfunction "2_2") (pintype "passive"))
    )
    (net (code "81") (name "Net-(D2-ANODE)") (class "Default")
      (node (ref "D2") (pin "1") (pinfunction "ANODE_1") (pintype "passive"))
      (node (ref "R1") (pin "2") (pinfunction "2_2") (pintype "passive"))
    )
    (net (code "82") (name "Net-(D3-ANODE)") (class "Default")
      (node (ref "D3") (pin "1") (pinfunction "ANODE_1") (pintype "passive"))
      (node (ref "R39") (pin "1") (pinfunction "1_1") (pintype "passive"))
    )
    (net (code "83") (name "Net-(D5-ANODE)") (class "Default")
      (node (ref "D5") (pin "1") (pinfunction "ANODE_1") (pintype "passive"))
      (node (ref "R41") (pin "1") (pinfunction "1_1") (pintype "passive"))
    )
    (net (code "84") (name "Net-(D6-ANODE)") (class "Default")
      (node (ref "D6") (pin "1") (pinfunction "ANODE_1") (pintype "passive"))
      (node (ref "R42") (pin "1") (pinfunction "1_1") (pintype "passive"))
    )
    (net (code "85") (name "Net-(D7-ANODE)") (class "Default")
      (node (ref "D7") (pin "1") (pinfunction "ANODE_1") (pintype "passive"))
      (node (ref "R43") (pin "1") (pinfunction "1_1") (pintype "passive"))
    )
    (net (code "86") (name "Net-(D8-ANODE)") (class "Default")
      (node (ref "D8") (pin "1") (pinfunction "ANODE_1") (pintype "passive"))
      (node (ref "R44") (pin "1") (pinfunction "1_1") (pintype "passive"))
    )
    (net (code "87") (name "Net-(J1-TIP)") (class "Default")
      (node (ref "F1") (pin "1") (pinfunction "1_1") (pintype "passive"))
      (node (ref "J1") (pin "1") (pinfunction "TIP_1") (pintype "power_in"))
    )
    (net (code "88") (name "Net-(U1C-CMPCS_B_2)") (class "Default")
      (node (ref "R45") (pin "1") (pinfunction "1_1") (pintype "passive"))
      (node (ref "U1") (pin "P72") (pinfunction "CMPCS_B_2_P72") (pintype "bidirectional"))
    )
    (net (code "89") (name "Net-(U1E-TCK)") (class "Default")
      (node (ref "R5") (pin "1") (pinfunction "1_1") (pintype "passive"))
      (node (ref "U1") (pin "P109") (pinfunction "TCK_P109") (pintype "input"))
    )
    (net (code "90") (name "Net-(U1E-TDI)") (class "Default")
      (node (ref "R2") (pin "1") (pinfunction "1_1") (pintype "passive"))
      (node (ref "U1") (pin "P110") (pinfunction "TDI_P110") (pintype "input"))
    )
    (net (code "91") (name "Net-(U1E-TDO)") (class "Default")
      (node (ref "R4") (pin "1") (pinfunction "1_1") (pintype "passive"))
      (node (ref "U1") (pin "P106") (pinfunction "TDO_P106") (pintype "output"))
    )
    (net (code "92") (name "Net-(U1E-TMS)") (class "Default")
      (node (ref "R7") (pin "1") (pinfunction "1_1") (pintype "passive"))
      (node (ref "U1") (pin "P107") (pinfunction "TMS_P107") (pintype "input"))
    )
    (net (code "93") (name "Net-(U2-DQ0{slash}SDI)") (class "Default")
      (node (ref "R9") (pin "2") (pinfunction "2_2") (pintype "passive"))
      (node (ref "U2") (pin "5") (pinfunction "DQ0/SDI_5") (pintype "passive"))
    )
    (net (code "94") (name "Net-(U2-DQ1{slash}SDO)") (class "Default")
      (node (ref "R10") (pin "2") (pinfunction "2_2") (pintype "passive"))
      (node (ref "U2") (pin "2") (pinfunction "DQ1/SDO_2") (pintype "passive"))
    )
    (net (code "95") (name "Net-(U2-DQ2{slash}WP#)") (class "Default")
      (node (ref "R11") (pin "2") (pinfunction "2_2") (pintype "passive"))
      (node (ref "R12") (pin "2") (pinfunction "2_2") (pintype "passive"))
      (node (ref "U2") (pin "3") (pinfunction "DQ2/WP#_3") (pintype "passive"))
    )
    (net (code "96") (name "Net-(U2-DQ3{slash}HOLD#)") (class "Default")
      (node (ref "R13") (pin "2") (pinfunction "2_2") (pintype "passive"))
      (node (ref "U2") (pin "7") (pinfunction "DQ3/HOLD#_7") (pintype "passive"))
    )
    (net (code "97") (name "Net-(U2-SCK)") (class "Default")
      (node (ref "R8") (pin "2") (pinfunction "2_2") (pintype "passive"))
      (node (ref "U2") (pin "6") (pinfunction "SCK_6") (pintype "passive"))
    )
    (net (code "98") (name "Net-(U5-OUT)") (class "Default")
      (node (ref "R16") (pin "2") (pinfunction "2_2") (pintype "passive"))
      (node (ref "U5") (pin "3") (pinfunction "OUT_3") (pintype "passive"))
    )
    (net (code "99") (name "VCC") (class "Default")
      (node (ref "C6") (pin "1") (pinfunction "1_1") (pintype "passive"))
      (node (ref "C7") (pin "1") (pinfunction "1_1") (pintype "passive"))
      (node (ref "D1") (pin "2") (pinfunction "2_2") (pintype "passive"))
      (node (ref "R1") (pin "1") (pinfunction "1_1") (pintype "passive"))
      (node (ref "U3") (pin "3") (pinfunction "VIN_3") (pintype "passive"))
      (node (ref "U4") (pin "3") (pinfunction "VIN_3") (pintype "passive"))
    )
    (net (code "100") (name "unconnected-(I1-Pad12)") (class "Default")
      (node (ref "I1") (pin "12") (pinfunction "12_12") (pintype "passive+no_connect"))
    )
    (net (code "101") (name "unconnected-(I1-Pad14)") (class "Default")
      (node (ref "I1") (pin "14") (pinfunction "14_14") (pintype "passive+no_connect"))
    )
    (net (code "102") (name "unconnected-(M1-Pad1)") (class "Default")
      (node (ref "M1") (pin "1") (pinfunction "1_1") (pintype "passive+no_connect"))
    )
    (net (code "103") (name "unconnected-(M2-Pad1)") (class "Default")
      (node (ref "M2") (pin "1") (pinfunction "1_1") (pintype "passive+no_connect"))
    )
    (net (code "104") (name "unconnected-(M3-Pad1)") (class "Default")
      (node (ref "M3") (pin "1") (pinfunction "1_1") (pintype "passive+no_connect"))
    )
    (net (code "105") (name "unconnected-(M4-Pad1)") (class "Default")
      (node (ref "M4") (pin "1") (pinfunction "1_1") (pintype "passive+no_connect"))
    )
    (net (code "106") (name "unconnected-(U1A-IO_L1P_HSWAPEN_0-PadP144)") (class "Default")
      (node (ref "U1") (pin "P144") (pinfunction "IO_L1P_HSWAPEN_0_P144") (pintype "bidirectional+no_connect"))
    )
    (net (code "107") (name "unconnected-(U1A-IO_L36P_GCLK15_0-PadP127)") (class "Default")
      (node (ref "U1") (pin "P127") (pinfunction "IO_L36P_GCLK15_0_P127") (pintype "bidirectional+no_connect"))
    )
    (net (code "108") (name "unconnected-(U1B-IO_L1N_VREF_1-PadP104)") (class "Default")
      (node (ref "U1") (pin "P104") (pinfunction "IO_L1N_VREF_1_P104") (pintype "bidirectional+no_connect"))
    )
    (net (code "109") (name "unconnected-(U1B-IO_L1P_1-PadP105)") (class "Default")
      (node (ref "U1") (pin "P105") (pinfunction "IO_L1P_1_P105") (pintype "bidirectional+no_connect"))
    )
    (net (code "110") (name "unconnected-(U1B-IO_L42N_GCLK6_TRDY1_1-PadP87)") (class "Default")
      (node (ref "U1") (pin "P87") (pinfunction "IO_L42N_GCLK6_TRDY1_1_P87") (pintype "bidirectional+no_connect"))
    )
    (net (code "111") (name "unconnected-(U1B-IO_L42P_GCLK7_1-PadP88)") (class "Default")
      (node (ref "U1") (pin "P88") (pinfunction "IO_L42P_GCLK7_1_P88") (pintype "bidirectional+no_connect"))
    )
    (net (code "112") (name "unconnected-(U1B-IO_L43N_GCLK4_1-PadP84)") (class "Default")
      (node (ref "U1") (pin "P84") (pinfunction "IO_L43N_GCLK4_1_P84") (pintype "bidirectional+no_connect"))
    )
    (net (code "113") (name "unconnected-(U1B-IO_L43P_GCLK5_1-PadP85)") (class "Default")
      (node (ref "U1") (pin "P85") (pinfunction "IO_L43P_GCLK5_1_P85") (pintype "bidirectional+no_connect"))
    )
    (net (code "114") (name "unconnected-(U1B-IO_L45N_1-PadP82)") (class "Default")
      (node (ref "U1") (pin "P82") (pinfunction "IO_L45N_1_P82") (pintype "bidirectional+no_connect"))
    )
    (net (code "115") (name "unconnected-(U1B-IO_L45P_1-PadP83)") (class "Default")
      (node (ref "U1") (pin "P83") (pinfunction "IO_L45P_1_P83") (pintype "bidirectional+no_connect"))
    )
    (net (code "116") (name "unconnected-(U1B-IO_L46N_1-PadP80)") (class "Default")
      (node (ref "U1") (pin "P80") (pinfunction "IO_L46N_1_P80") (pintype "bidirectional+no_connect"))
    )
    (net (code "117") (name "unconnected-(U1B-IO_L46P_1-PadP81)") (class "Default")
      (node (ref "U1") (pin "P81") (pinfunction "IO_L46P_1_P81") (pintype "bidirectional+no_connect"))
    )
    (net (code "118") (name "unconnected-(U1B-IO_L74N_DOUT_BUSY_1-PadP74)") (class "Default")
      (node (ref "U1") (pin "P74") (pinfunction "IO_L74N_DOUT_BUSY_1_P74") (pintype "bidirectional+no_connect"))
    )
    (net (code "119") (name "unconnected-(U1B-IO_L74P_AWAKE_1-PadP75)") (class "Default")
      (node (ref "U1") (pin "P75") (pinfunction "IO_L74P_AWAKE_1_P75") (pintype "bidirectional+no_connect"))
    )
    (net (code "120") (name "unconnected-(U1C-IO_L2N_CMPMOSI_2-PadP66)") (class "Default")
      (node (ref "U1") (pin "P66") (pinfunction "IO_L2N_CMPMOSI_2_P66") (pintype "bidirectional+no_connect"))
    )
    (net (code "121") (name "unconnected-(U1C-IO_L12N_D2_MISO3_2-PadP61)") (class "Default")
      (node (ref "U1") (pin "P61") (pinfunction "IO_L12N_D2_MISO3_2_P61") (pintype "bidirectional+no_connect"))
    )
    (net (code "122") (name "unconnected-(U1C-IO_L12P_D1_MISO2_2-PadP62)") (class "Default")
      (node (ref "U1") (pin "P62") (pinfunction "IO_L12P_D1_MISO2_2_P62") (pintype "bidirectional+no_connect"))
    )
    (net (code "123") (name "unconnected-(U1C-IO_L13N_D10_2-PadP59)") (class "Default")
      (node (ref "U1") (pin "P59") (pinfunction "IO_L13N_D10_2_P59") (pintype "bidirectional+no_connect"))
    )
    (net (code "124") (name "unconnected-(U1C-IO_L14N_D12_2-PadP57)") (class "Default")
      (node (ref "U1") (pin "P57") (pinfunction "IO_L14N_D12_2_P57") (pintype "bidirectional+no_connect"))
    )
    (net (code "125") (name "unconnected-(U1C-IO_L14P_D11_2-PadP58)") (class "Default")
      (node (ref "U1") (pin "P58") (pinfunction "IO_L14P_D11_2_P58") (pintype "bidirectional+no_connect"))
    )
    (net (code "126") (name "unconnected-(U1C-IO_L30N_GCLK0_USERCCLK_2-PadP55)") (class "Default")
      (node (ref "U1") (pin "P55") (pinfunction "IO_L30N_GCLK0_USERCCLK_2_P55") (pintype "bidirectional+no_connect"))
    )
    (net (code "127") (name "unconnected-(U1C-IO_L30P_GCLK1_D13_2-PadP56)") (class "Default")
      (node (ref "U1") (pin "P56") (pinfunction "IO_L30P_GCLK1_D13_2_P56") (pintype "bidirectional+no_connect"))
    )
    (net (code "128") (name "unconnected-(U1C-IO_L31P_GCLK31_D14_2-PadP51)") (class "Default")
      (node (ref "U1") (pin "P51") (pinfunction "IO_L31P_GCLK31_D14_2_P51") (pintype "bidirectional+no_connect"))
    )
    (net (code "129") (name "unconnected-(U1C-IO_L48N_RDWR_B_VREF_2-PadP47)") (class "Default")
      (node (ref "U1") (pin "P47") (pinfunction "IO_L48N_RDWR_B_VREF_2_P47") (pintype "bidirectional+no_connect"))
    )
    (net (code "130") (name "unconnected-(U1C-IO_L48P_D7_2-PadP48)") (class "Default")
      (node (ref "U1") (pin "P48") (pinfunction "IO_L48P_D7_2_P48") (pintype "bidirectional+no_connect"))
    )
    (net (code "131") (name "unconnected-(U1C-IO_L49N_D4_2-PadP45)") (class "Default")
      (node (ref "U1") (pin "P45") (pinfunction "IO_L49N_D4_2_P45") (pintype "bidirectional+no_connect"))
    )
    (net (code "132") (name "unconnected-(U1C-IO_L49P_D3_2-PadP46)") (class "Default")
      (node (ref "U1") (pin "P46") (pinfunction "IO_L49P_D3_2_P46") (pintype "bidirectional+no_connect"))
    )
    (net (code "133") (name "unconnected-(U1C-IO_L62N_D6_2-PadP43)") (class "Default")
      (node (ref "U1") (pin "P43") (pinfunction "IO_L62N_D6_2_P43") (pintype "bidirectional+no_connect"))
    )
    (net (code "134") (name "unconnected-(U1C-IO_L62P_D5_2-PadP44)") (class "Default")
      (node (ref "U1") (pin "P44") (pinfunction "IO_L62P_D5_2_P44") (pintype "bidirectional+no_connect"))
    )
    (net (code "135") (name "unconnected-(U1C-IO_L64P_D8_2-PadP41)") (class "Default")
      (node (ref "U1") (pin "P41") (pinfunction "IO_L64P_D8_2_P41") (pintype "bidirectional+no_connect"))
    )
    (net (code "136") (name "unconnected-(U1D-IO_L43N_GCLK22_IRDY2_3-PadP16)") (class "Default")
      (node (ref "U1") (pin "P16") (pinfunction "IO_L43N_GCLK22_IRDY2_3_P16") (pintype "bidirectional+no_connect"))
    )
    (net (code "137") (name "unconnected-(U1E-SUSPEND-PadP73)") (class "Default")
      (node (ref "U1") (pin "P73") (pinfunction "SUSPEND_P73") (pintype "bidirectional+no_connect"))
    )
  )
)
